# Power_LDO_2V5.net
KiCad netlist of a schematic drawn in Altium Designer
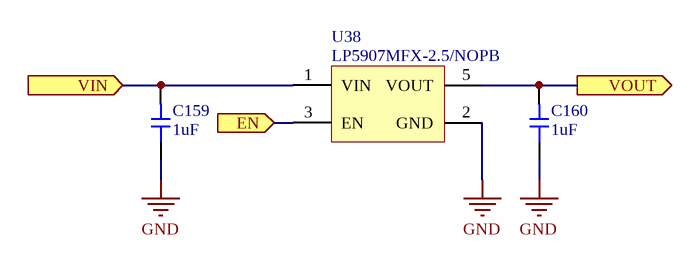
[diagram p0: Power_LDO_2V5.SchDoc]

(export (version "E")
  (design (tool "Eeschema 10.0.6"))
  (components
    (comp (ref "C159")
      (value "1uF")
      (footprint "0603-CAP")
      (description "Capacitor")
      (fields
        (field (name "MANUFACTURER") "Samsung")
        (field (name "MANUFACTURER PART NUMBER") "CL10B105MO8NNWC")
      )
      (libsource (lib "AMDC") (part "Capacitor"))
    )
    (comp (ref "C160")
      (value "1uF")
      (footprint "0603-CAP")
      (description "Capacitor")
      (fields
        (field (name "MANUFACTURER") "Samsung")
        (field (name "MANUFACTURER PART NUMBER") "CL10B105MO8NNWC")
      )
      (libsource (lib "AMDC") (part "Capacitor"))
    )
    (comp (ref "U38")
      (value "LP5907MFX-2.5/NOPB")
      (footprint "SOT23-5")
      (description "IC REG LINEAR 2.5V 250MA SOT23")
      (libsource (lib "AMDC") (part "LP5907MFX-2.5/NOPB"))
    )
  )
  (nets
    (net (code "1") (name "/EN") (class "Default")
      (node (ref "U38") (pin "3") (pinfunction "EN_3") (pintype "passive"))
    )
    (net (code "2") (name "/VIN") (class "Default")
      (node (ref "C159") (pin "1") (pinfunction "1_1") (pintype "passive"))
      (node (ref "U38") (pin "1") (pinfunction "VIN_1") (pintype "passive"))
    )
    (net (code "3") (name "/VOUT") (class "Default")
      (node (ref "C160") (pin "1") (pinfunction "1_1") (pintype "passive"))
      (node (ref "U38") (pin "5") (pinfunction "VOUT_5") (pintype "passive"))
    )
    (net (code "4") (name "GND") (class "Default")
      (node (ref "C159") (pin "2") (pinfunction "2_2") (pintype "passive"))
      (node (ref "C160") (pin "2") (pinfunction "2_2") (pintype "passive"))
      (node (ref "U38") (pin "2") (pinfunction "GND_2") (pintype "passive"))
    )
  )
)
